# CTR-Controller-Rev-A-Sensors-4.net
KiCad netlist of a schematic drawn in Altium Designer
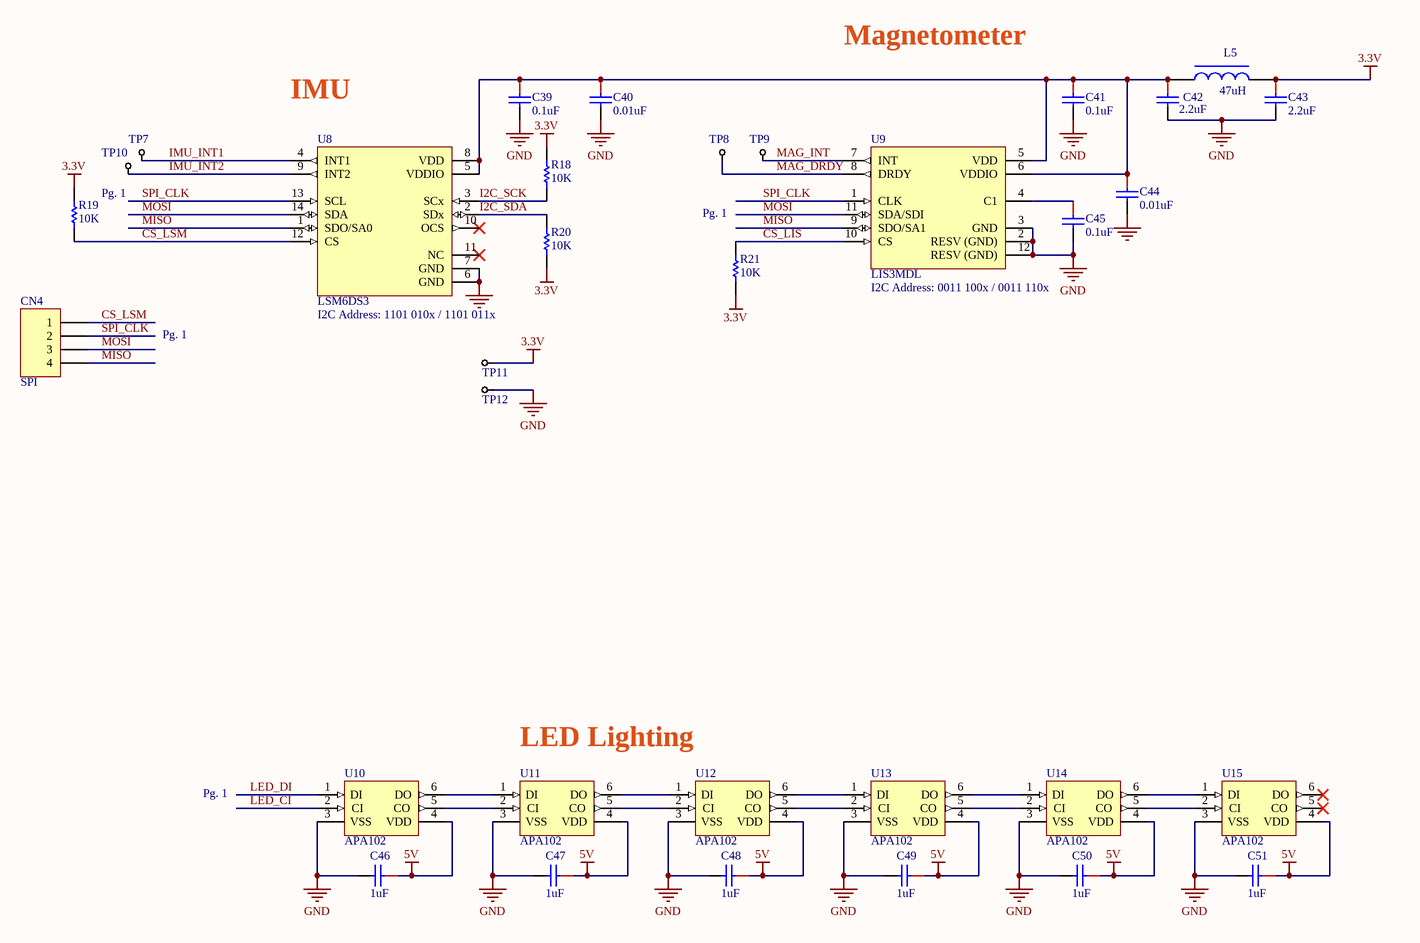
[diagram p0: CTR-Controller-Rev-A-Sensors-4.SchDoc]

(export (version "E")
  (design (tool "Eeschema 10.0.6"))
  (components
    (comp (ref "C39")
      (value "0.1uF")
      (footprint "CAPC0402(1005)_N")
      (description "0.1uF 0402 50V")
      (fields
        (field (name "MANUFACTURER") "TDK Corporation")
        (field (name "MANUFACTURER PART NUMBER") "CGA2B3X7R1H104K050BB")
        (field (name "CREATOR") "osman")
      )
      (libsource (lib "OLogic-Passive") (part "CAP CER 0.1UF 50V 10% X7R 0402"))
    )
    (comp (ref "C40")
      (value "0.01uF")
      (footprint "CAPC0402(1005)_N")
      (description "0.01uF 0402")
      (fields
        (field (name "MANUFACTURER") "Murata Electronics North America")
        (field (name "MANUFACTURER PART NUMBER") "GRM155R71E103KA01D")
      )
      (libsource (lib "OLogic-Passive") (part "CAP CER 0.01UF 25V 10% X5R 0402"))
    )
    (comp (ref "C41")
      (value "0.1uF")
      (footprint "CAPC0402(1005)_N")
      (description "0.1uF 0402 50V")
      (fields
        (field (name "MANUFACTURER") "TDK Corporation")
        (field (name "MANUFACTURER PART NUMBER") "CGA2B3X7R1H104K050BB")
        (field (name "CREATOR") "osman")
      )
      (libsource (lib "OLogic-Passive") (part "CAP CER 0.1UF 50V 10% X7R 0402"))
    )
    (comp (ref "C42")
      (value "2.2uF")
      (footprint "CAPC0402(1005)_N")
      (description "2.2uF 0402")
      (fields
        (field (name "MANUFACTURER") "TDK Corporation")
        (field (name "MANUFACTURER PART NUMBER") "C1005X5R1V225K050BC")
        (field (name "CREATOR") "osman")
      )
      (libsource (lib "OLogic-Passive") (part "CAP CER 2.2UF 35V 10% X5R 0402"))
    )
    (comp (ref "C43")
      (value "2.2uF")
      (footprint "CAPC0402(1005)_N")
      (description "2.2uF 0402")
      (fields
        (field (name "MANUFACTURER") "TDK Corporation")
        (field (name "MANUFACTURER PART NUMBER") "C1005X5R1V225K050BC")
        (field (name "CREATOR") "osman")
      )
      (libsource (lib "OLogic-Passive") (part "CAP CER 2.2UF 35V 10% X5R 0402"))
    )
    (comp (ref "C44")
      (value "0.01uF")
      (footprint "CAPC0402(1005)_N")
      (description "0.01uF 0402")
      (fields
        (field (name "MANUFACTURER") "Murata Electronics North America")
        (field (name "MANUFACTURER PART NUMBER") "GRM155R71E103KA01D")
      )
      (libsource (lib "OLogic-Passive") (part "CAP CER 0.01UF 25V 10% X5R 0402"))
    )
    (comp (ref "C45")
      (value "0.1uF")
      (footprint "CAPC0402(1005)_N")
      (description "0.1uF 0402 50V")
      (fields
        (field (name "MANUFACTURER") "TDK Corporation")
        (field (name "MANUFACTURER PART NUMBER") "CGA2B3X7R1H104K050BB")
        (field (name "CREATOR") "osman")
      )
      (libsource (lib "OLogic-Passive") (part "CAP CER 0.1UF 50V 10% X7R 0402"))
    )
    (comp (ref "C46")
      (value "1uF")
      (footprint "CAPC0402(1005)_N")
      (description "1UF 0402")
      (fields
        (field (name "MANUFACTURER") "TDK Corporation")
        (field (name "MANUFACTURER PART NUMBER") "C1005X5R1C105K050BC")
      )
      (libsource (lib "OLogic-Passive") (part "CAP CER 1UF 16V 10% X5R 0402"))
    )
    (comp (ref "C47")
      (value "1uF")
      (footprint "CAPC0402(1005)_N")
      (description "1UF 0402")
      (fields
        (field (name "MANUFACTURER") "TDK Corporation")
        (field (name "MANUFACTURER PART NUMBER") "C1005X5R1C105K050BC")
      )
      (libsource (lib "OLogic-Passive") (part "CAP CER 1UF 16V 10% X5R 0402"))
    )
    (comp (ref "C48")
      (value "1uF")
      (footprint "CAPC0402(1005)_N")
      (description "1UF 0402")
      (fields
        (field (name "MANUFACTURER") "TDK Corporation")
        (field (name "MANUFACTURER PART NUMBER") "C1005X5R1C105K050BC")
      )
      (libsource (lib "OLogic-Passive") (part "CAP CER 1UF 16V 10% X5R 0402"))
    )
    (comp (ref "C49")
      (value "1uF")
      (footprint "CAPC0402(1005)_N")
      (description "1UF 0402")
      (fields
        (field (name "MANUFACTURER") "TDK Corporation")
        (field (name "MANUFACTURER PART NUMBER") "C1005X5R1C105K050BC")
      )
      (libsource (lib "OLogic-Passive") (part "CAP CER 1UF 16V 10% X5R 0402"))
    )
    (comp (ref "C50")
      (value "1uF")
      (footprint "CAPC0402(1005)_N")
      (description "1UF 0402")
      (fields
        (field (name "MANUFACTURER") "TDK Corporation")
        (field (name "MANUFACTURER PART NUMBER") "C1005X5R1C105K050BC")
      )
      (libsource (lib "OLogic-Passive") (part "CAP CER 1UF 16V 10% X5R 0402"))
    )
    (comp (ref "C51")
      (value "1uF")
      (footprint "CAPC0402(1005)_N")
      (description "1UF 0402")
      (fields
        (field (name "MANUFACTURER") "TDK Corporation")
        (field (name "MANUFACTURER PART NUMBER") "C1005X5R1C105K050BC")
      )
      (libsource (lib "OLogic-Passive") (part "CAP CER 1UF 16V 10% X5R 0402"))
    )
    (comp (ref "CN4")
      (value "SPI")
      (footprint "HDR1X4")
      (description "Header, 4-Pin")
      (fields
        (field (name "MANUFACTURER") "Sullins Connector Solutions")
        (field (name "MANUFACTURER PART NUMBER") "PRPC004SAAN-RC")
      )
      (libsource (lib "OLogic-Connectors") (part "Header 4"))
    )
    (comp (ref "L5")
      (value "47uH")
      (footprint "IND-2012 Chip")
      (description "47uH 0805")
      (fields
        (field (name "MANUFACTURER") "TDK Corporation")
        (field (name "MANUFACTURER PART NUMBER") "MLZ2012M470WT000")
      )
      (libsource (lib "OLogic-Passive") (part "INDUCTOR MULTILAYER 47UH 100mA 0805"))
    )
    (comp (ref "R18")
      (value "10K")
      (footprint "RESC0402(1005)_N")
      (description "10K 0402")
      (fields
        (field (name "MANUFACTURER") "Panasonic Electronic Components")
        (field (name "MANUFACTURER PART NUMBER") "ERJ-2GEJ103X")
        (field (name "CREATOR") "ted")
      )
      (libsource (lib "OLogic-Passive") (part "RES 10K OHM 5% 1/10W 0402"))
    )
    (comp (ref "R19")
      (value "10K")
      (footprint "RESC0402(1005)_N")
      (description "10K 0402")
      (fields
        (field (name "MANUFACTURER") "Panasonic Electronic Components")
        (field (name "MANUFACTURER PART NUMBER") "ERJ-2GEJ103X")
        (field (name "CREATOR") "ted")
      )
      (libsource (lib "OLogic-Passive") (part "RES 10K OHM 5% 1/10W 0402"))
    )
    (comp (ref "R20")
      (value "10K")
      (footprint "RESC0402(1005)_N")
      (description "10K 0402")
      (fields
        (field (name "MANUFACTURER") "Panasonic Electronic Components")
        (field (name "MANUFACTURER PART NUMBER") "ERJ-2GEJ103X")
        (field (name "CREATOR") "ted")
      )
      (libsource (lib "OLogic-Passive") (part "RES 10K OHM 5% 1/10W 0402"))
    )
    (comp (ref "R21")
      (value "10K")
      (footprint "RESC0402(1005)_N")
      (description "10K 0402")
      (fields
        (field (name "MANUFACTURER") "Panasonic Electronic Components")
        (field (name "MANUFACTURER PART NUMBER") "ERJ-2GEJ103X")
        (field (name "CREATOR") "ted")
      )
      (libsource (lib "OLogic-Passive") (part "RES 10K OHM 5% 1/10W 0402"))
    )
    (comp (ref "TP7")
      (value "Test Point")
      (footprint "TestPoint-TH 42 mil")
      (libsource (lib "OLogic-Misc") (part "TestPoint, small"))
    )
    (comp (ref "TP8")
      (value "Test Point")
      (footprint "TestPoint-TH 42 mil")
      (libsource (lib "OLogic-Misc") (part "TestPoint, small"))
    )
    (comp (ref "TP9")
      (value "Test Point")
      (footprint "TestPoint-TH 42 mil")
      (libsource (lib "OLogic-Misc") (part "TestPoint, small"))
    )
    (comp (ref "TP10")
      (value "Test Point")
      (footprint "TestPoint-TH 42 mil")
      (libsource (lib "OLogic-Misc") (part "TestPoint, small"))
    )
    (comp (ref "TP11")
      (value "3V")
      (footprint "TestPoint-TH 35 mil")
      (description "Test Point")
      (libsource (lib "OLogic-Misc") (part "TestPoint, small"))
    )
    (comp (ref "TP12")
      (value "GND")
      (footprint "TestPoint-TH 35 mil")
      (description "Test Point")
      (libsource (lib "OLogic-Misc") (part "TestPoint, small"))
    )
    (comp (ref "U8")
      (value "LSM6DS3")
      (footprint "LSM6DS3")
      (description "3D ACC/GYRO INEMO 14VFLGA")
      (fields
        (field (name "MANUFACTURER") "STMicroelectronics")
        (field (name "MANUFACTURER PART NUMBER") "LSM6DS3")
        (field (name "I2C ADDRESS") "1101 010x / 1101 011x")
        (field (name "CREATOR") "osman")
      )
      (libsource (lib "OLogic-Sensors") (part "LSM6DS3"))
    )
    (comp (ref "U9")
      (value "LIS3MDL")
      (footprint "LIS3MDL")
      (description "IC MAGNETOMETER 3-AXIS 12LGA")
      (fields
        (field (name "MANUFACTURER") "STMicroelectronics")
        (field (name "MANUFACTURER PART NUMBER") "LIS3MDL")
        (field (name "I2C ADDRESS") "0011 100x / 0011 110x")
        (field (name "CREATOR") "osman")
      )
      (libsource (lib "OLogic-Sensors") (part "LIS3MDL"))
    )
    (comp (ref "U10")
      (value "APA102")
      (footprint "APA102C")
      (description "APA102 RGB LED with serial controller")
      (fields (field (name "MANUFACTURER") "Shiji Lighting") (field (name "MPN") "APA102C"))
      (libsource (lib "OLogic-Diode-Opto-LED") (part "APA102"))
    )
    (comp (ref "U11")
      (value "APA102")
      (footprint "APA102C")
      (description "APA102 RGB LED with serial controller")
      (fields (field (name "MANUFACTURER") "Shiji Lighting") (field (name "MPN") "APA102C"))
      (libsource (lib "OLogic-Diode-Opto-LED") (part "APA102"))
    )
    (comp (ref "U12")
      (value "APA102")
      (footprint "APA102C")
      (description "APA102 RGB LED with serial controller")
      (fields (field (name "MANUFACTURER") "Shiji Lighting") (field (name "MPN") "APA102C"))
      (libsource (lib "OLogic-Diode-Opto-LED") (part "APA102"))
    )
    (comp (ref "U13")
      (value "APA102")
      (footprint "APA102C")
      (description "APA102 RGB LED with serial controller")
      (fields (field (name "MANUFACTURER") "Shiji Lighting") (field (name "MPN") "APA102C"))
      (libsource (lib "OLogic-Diode-Opto-LED") (part "APA102"))
    )
    (comp (ref "U14")
      (value "APA102")
      (footprint "APA102C")
      (description "APA102 RGB LED with serial controller")
      (fields (field (name "MANUFACTURER") "Shiji Lighting") (field (name "MPN") "APA102C"))
      (libsource (lib "OLogic-Diode-Opto-LED") (part "APA102"))
    )
    (comp (ref "U15")
      (value "APA102")
      (footprint "APA102C")
      (description "APA102 RGB LED with serial controller")
      (fields (field (name "MANUFACTURER") "Shiji Lighting") (field (name "MPN") "APA102C"))
      (libsource (lib "OLogic-Diode-Opto-LED") (part "APA102"))
    )
  )
  (nets
    (net (code "1") (name "/CS_LIS") (class "Default")
      (node (ref "R21") (pin "2") (pinfunction "2_2") (pintype "passive"))
      (node (ref "U9") (pin "10") (pinfunction "CS_10") (pintype "input"))
    )
    (net (code "2") (name "/CS_LSM") (class "Default")
      (node (ref "CN4") (pin "1") (pinfunction "1_1") (pintype "passive"))
      (node (ref "R19") (pin "1") (pinfunction "1_1") (pintype "passive"))
      (node (ref "U8") (pin "12") (pinfunction "CS_12") (pintype "input"))
    )
    (net (code "3") (name "/I2C_SCK") (class "Default")
      (node (ref "R18") (pin "1") (pinfunction "1_1") (pintype "passive"))
      (node (ref "U8") (pin "3") (pinfunction "SCx_3") (pintype "input"))
    )
    (net (code "4") (name "/I2C_SDA") (class "Default")
      (node (ref "R20") (pin "2") (pinfunction "2_2") (pintype "passive"))
      (node (ref "U8") (pin "2") (pinfunction "SDx_2") (pintype "bidirectional"))
    )
    (net (code "5") (name "/IMU_INT1") (class "Default")
      (node (ref "TP7") (pin "1") (pinfunction "1_1") (pintype "passive"))
      (node (ref "U8") (pin "4") (pinfunction "INT1_4") (pintype "output"))
    )
    (net (code "6") (name "/IMU_INT2") (class "Default")
      (node (ref "TP10") (pin "1") (pinfunction "1_1") (pintype "passive"))
      (node (ref "U8") (pin "9") (pinfunction "INT2_9") (pintype "output"))
    )
    (net (code "7") (name "/LED_CI") (class "Default")
      (node (ref "U10") (pin "2") (pinfunction "CI_2") (pintype "input"))
    )
    (net (code "8") (name "/LED_DI") (class "Default")
      (node (ref "U10") (pin "1") (pinfunction "DI_1") (pintype "input"))
    )
    (net (code "9") (name "/MAG_DRDY") (class "Default")
      (node (ref "TP8") (pin "1") (pinfunction "1_1") (pintype "passive"))
      (node (ref "U9") (pin "8") (pinfunction "DRDY_8") (pintype "output"))
    )
    (net (code "10") (name "/MAG_INT") (class "Default")
      (node (ref "TP9") (pin "1") (pinfunction "1_1") (pintype "passive"))
      (node (ref "U9") (pin "7") (pinfunction "INT_7") (pintype "output"))
    )
    (net (code "11") (name "/MISO") (class "Default")
      (node (ref "CN4") (pin "4") (pinfunction "4_4") (pintype "passive"))
      (node (ref "U8") (pin "1") (pinfunction "SDO/SA0_1") (pintype "bidirectional"))
      (node (ref "U9") (pin "9") (pinfunction "SDO/SA1_9") (pintype "bidirectional"))
    )
    (net (code "12") (name "/MOSI") (class "Default")
      (node (ref "CN4") (pin "3") (pinfunction "3_3") (pintype "passive"))
      (node (ref "U8") (pin "14") (pinfunction "SDA_14") (pintype "bidirectional"))
      (node (ref "U9") (pin "11") (pinfunction "SDA/SDI_11") (pintype "bidirectional"))
    )
    (net (code "13") (name "/SPI_CLK") (class "Default")
      (node (ref "CN4") (pin "2") (pinfunction "2_2") (pintype "passive"))
      (node (ref "U8") (pin "13") (pinfunction "SCL_13") (pintype "input"))
      (node (ref "U9") (pin "1") (pinfunction "CLK_1") (pintype "input"))
    )
    (net (code "14") (name "3.3V") (class "Default")
      (node (ref "C43") (pin "1") (pinfunction "1_1") (pintype "passive"))
      (node (ref "L5") (pin "2") (pinfunction "2_2") (pintype "passive"))
      (node (ref "R18") (pin "2") (pinfunction "2_2") (pintype "passive"))
      (node (ref "R19") (pin "2") (pinfunction "2_2") (pintype "passive"))
      (node (ref "R20") (pin "1") (pinfunction "1_1") (pintype "passive"))
      (node (ref "R21") (pin "1") (pinfunction "1_1") (pintype "passive"))
      (node (ref "TP11") (pin "1") (pinfunction "1_1") (pintype "passive"))
    )
    (net (code "15") (name "5V") (class "Default")
      (node (ref "C46") (pin "1") (pinfunction "1_1") (pintype "passive"))
      (node (ref "C47") (pin "1") (pinfunction "1_1") (pintype "passive"))
      (node (ref "C48") (pin "1") (pinfunction "1_1") (pintype "passive"))
      (node (ref "C49") (pin "1") (pinfunction "1_1") (pintype "passive"))
      (node (ref "C50") (pin "1") (pinfunction "1_1") (pintype "passive"))
      (node (ref "C51") (pin "1") (pinfunction "1_1") (pintype "passive"))
      (node (ref "U10") (pin "4") (pinfunction "VDD_4") (pintype "power_in"))
      (node (ref "U11") (pin "4") (pinfunction "VDD_4") (pintype "power_in"))
      (node (ref "U12") (pin "4") (pinfunction "VDD_4") (pintype "power_in"))
      (node (ref "U13") (pin "4") (pinfunction "VDD_4") (pintype "power_in"))
      (node (ref "U14") (pin "4") (pinfunction "VDD_4") (pintype "power_in"))
      (node (ref "U15") (pin "4") (pinfunction "VDD_4") (pintype "power_in"))
    )
    (net (code "16") (name "GND") (class "Default")
      (node (ref "C39") (pin "2") (pinfunction "2_2") (pintype "passive"))
      (node (ref "C40") (pin "2") (pinfunction "2_2") (pintype "passive"))
      (node (ref "C41") (pin "2") (pinfunction "2_2") (pintype "passive"))
      (node (ref "C42") (pin "2") (pinfunction "2_2") (pintype "passive"))
      (node (ref "C43") (pin "2") (pinfunction "2_2") (pintype "passive"))
      (node (ref "C44") (pin "2") (pinfunction "2_2") (pintype "passive"))
      (node (ref "C45") (pin "2") (pinfunction "2_2") (pintype "passive"))
      (node (ref "C46") (pin "2") (pinfunction "2_2") (pintype "passive"))
      (node (ref "C47") (pin "2") (pinfunction "2_2") (pintype "passive"))
      (node (ref "C48") (pin "2") (pinfunction "2_2") (pintype "passive"))
      (node (ref "C49") (pin "2") (pinfunction "2_2") (pintype "passive"))
      (node (ref "C50") (pin "2") (pinfunction "2_2") (pintype "passive"))
      (node (ref "C51") (pin "2") (pinfunction "2_2") (pintype "passive"))
      (node (ref "TP12") (pin "1") (pinfunction "1_1") (pintype "passive"))
      (node (ref "U10") (pin "3") (pinfunction "VSS_3") (pintype "power_in"))
      (node (ref "U11") (pin "3") (pinfunction "VSS_3") (pintype "power_in"))
      (node (ref "U12") (pin "3") (pinfunction "VSS_3") (pintype "power_in"))
      (node (ref "U13") (pin "3") (pinfunction "VSS_3") (pintype "power_in"))
      (node (ref "U14") (pin "3") (pinfunction "VSS_3") (pintype "power_in"))
      (node (ref "U15") (pin "3") (pinfunction "VSS_3") (pintype "power_in"))
      (node (ref "U8") (pin "6") (pinfunction "GND_6") (pintype "power_in"))
      (node (ref "U8") (pin "7") (pinfunction "GND_7") (pintype "power_in"))
      (node (ref "U9") (pin "12") (pinfunction "RESV_(GND)_12") (pintype "power_in"))
      (node (ref "U9") (pin "2") (pinfunction "RESV_(GND)_2") (pintype "power_in"))
      (node (ref "U9") (pin "3") (pinfunction "GND_3") (pintype "power_in"))
    )
    (net (code "17") (name "Net-(U8-VDD)") (class "Default")
      (node (ref "C39") (pin "1") (pinfunction "1_1") (pintype "passive"))
      (node (ref "C40") (pin "1") (pinfunction "1_1") (pintype "passive"))
      (node (ref "C41") (pin "1") (pinfunction "1_1") (pintype "passive"))
      (node (ref "C42") (pin "1") (pinfunction "1_1") (pintype "passive"))
      (node (ref "C44") (pin "1") (pinfunction "1_1") (pintype "passive"))
      (node (ref "L5") (pin "1") (pinfunction "1_1") (pintype "passive"))
      (node (ref "U8") (pin "5") (pinfunction "VDDIO_5") (pintype "power_in"))
      (node (ref "U8") (pin "8") (pinfunction "VDD_8") (pintype "power_in"))
      (node (ref "U9") (pin "5") (pinfunction "VDD_5") (pintype "power_in"))
      (node (ref "U9") (pin "6") (pinfunction "VDDIO_6") (pintype "power_in"))
    )
    (net (code "18") (name "Net-(U9-C1)") (class "Default")
      (node (ref "C45") (pin "1") (pinfunction "1_1") (pintype "passive"))
      (node (ref "U9") (pin "4") (pinfunction "C1_4") (pintype "power_in"))
    )
    (net (code "19") (name "Net-(U10-CO)") (class "Default")
      (node (ref "U10") (pin "5") (pinfunction "CO_5") (pintype "output"))
      (node (ref "U11") (pin "2") (pinfunction "CI_2") (pintype "input"))
    )
    (net (code "20") (name "Net-(U10-DO)") (class "Default")
      (node (ref "U10") (pin "6") (pinfunction "DO_6") (pintype "output"))
      (node (ref "U11") (pin "1") (pinfunction "DI_1") (pintype "input"))
    )
    (net (code "21") (name "Net-(U11-CO)") (class "Default")
      (node (ref "U11") (pin "5") (pinfunction "CO_5") (pintype "output"))
      (node (ref "U12") (pin "2") (pinfunction "CI_2") (pintype "input"))
    )
    (net (code "22") (name "Net-(U11-DO)") (class "Default")
      (node (ref "U11") (pin "6") (pinfunction "DO_6") (pintype "output"))
      (node (ref "U12") (pin "1") (pinfunction "DI_1") (pintype "input"))
    )
    (net (code "23") (name "Net-(U12-CO)") (class "Default")
      (node (ref "U12") (pin "5") (pinfunction "CO_5") (pintype "output"))
      (node (ref "U13") (pin "2") (pinfunction "CI_2") (pintype "input"))
    )
    (net (code "24") (name "Net-(U12-DO)") (class "Default")
      (node (ref "U12") (pin "6") (pinfunction "DO_6") (pintype "output"))
      (node (ref "U13") (pin "1") (pinfunction "DI_1") (pintype "input"))
    )
    (net (code "25") (name "Net-(U13-CO)") (class "Default")
      (node (ref "U13") (pin "5") (pinfunction "CO_5") (pintype "output"))
      (node (ref "U14") (pin "2") (pinfunction "CI_2") (pintype "input"))
    )
    (net (code "26") (name "Net-(U13-DO)") (class "Default")
      (node (ref "U13") (pin "6") (pinfunction "DO_6") (pintype "output"))
      (node (ref "U14") (pin "1") (pinfunction "DI_1") (pintype "input"))
    )
    (net (code "27") (name "Net-(U14-CO)") (class "Default")
      (node (ref "U14") (pin "5") (pinfunction "CO_5") (pintype "output"))
      (node (ref "U15") (pin "2") (pinfunction "CI_2") (pintype "input"))
    )
    (net (code "28") (name "Net-(U14-DO)") (class "Default")
      (node (ref "U14") (pin "6") (pinfunction "DO_6") (pintype "output"))
      (node (ref "U15") (pin "1") (pinfunction "DI_1") (pintype "input"))
    )
    (net (code "29") (name "unconnected-(U8-NC-Pad11)") (class "Default")
      (node (ref "U8") (pin "11") (pinfunction "NC_11") (pintype "passive+no_connect"))
    )
    (net (code "30") (name "unconnected-(U8-OCS-Pad10)") (class "Default")
      (node (ref "U8") (pin "10") (pinfunction "OCS_10") (pintype "output+no_connect"))
    )
    (net (code "31") (name "unconnected-(U15-CO-Pad5)") (class "Default")
      (node (ref "U15") (pin "5") (pinfunction "CO_5") (pintype "output+no_connect"))
    )
    (net (code "32") (name "unconnected-(U15-DO-Pad6)") (class "Default")
      (node (ref "U15") (pin "6") (pinfunction "DO_6") (pintype "output+no_connect"))
    )
  )
)
